# VCO.net
KiCad netlist of a schematic drawn in Altium Designer
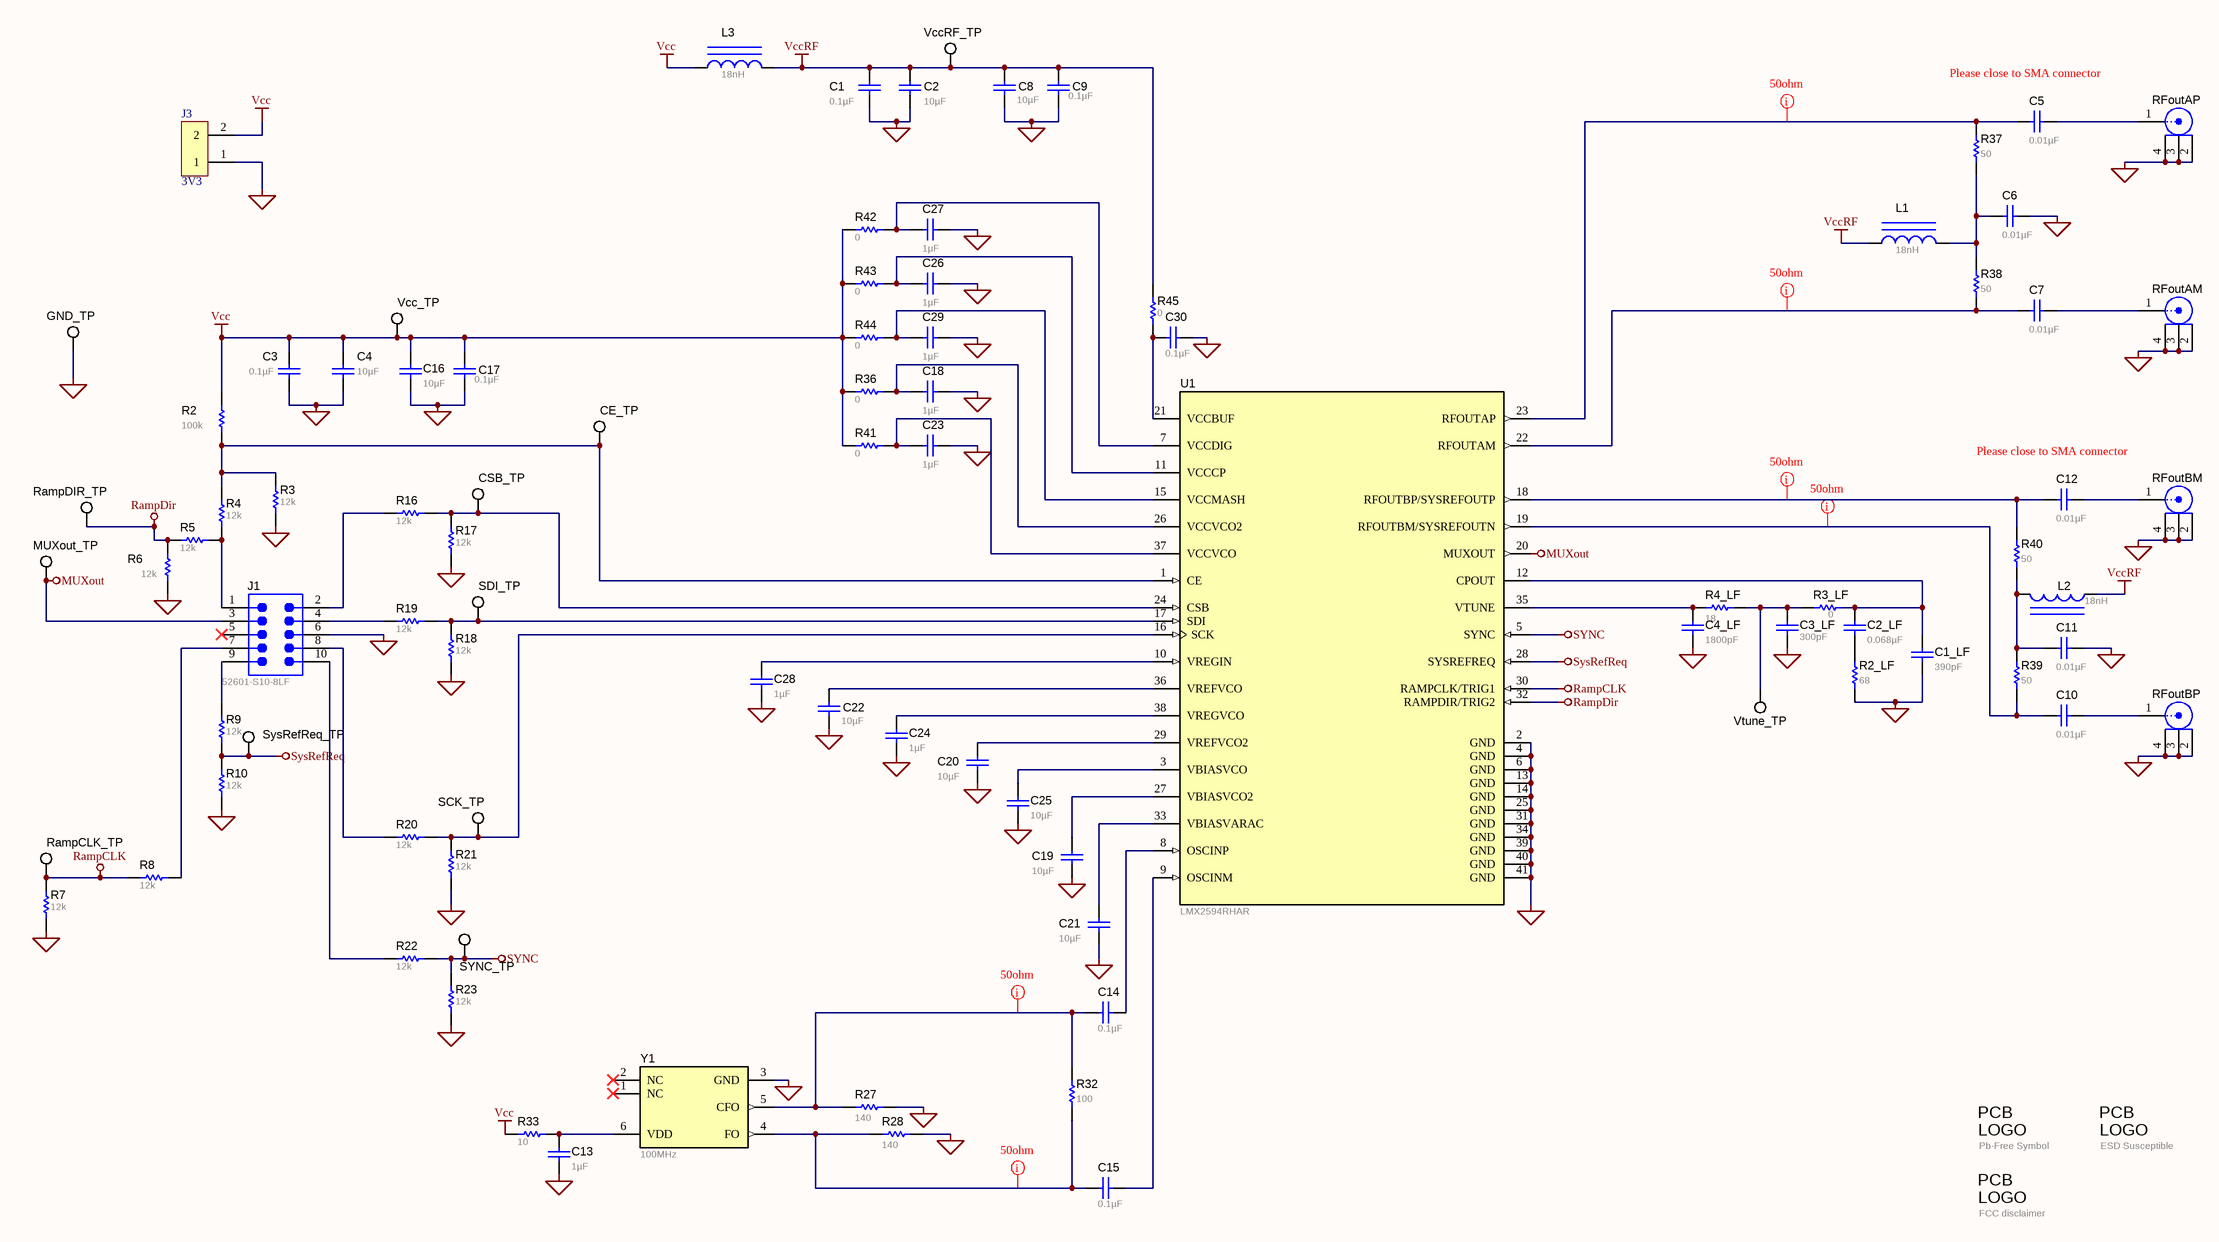
[diagram p0: VCO.SchDoc]

(export (version "E")
  (design (tool "Eeschema 10.0.6"))
  (components
    (comp (ref "C1")
      (value "0603YC104JAT2A")
      (footprint "0603")
      (description "CAP, CERM, 0.1uF, 16V, +/-5%, X7R, 0603")
      (fields
        (field (name "MANUFACTURER") "AVX")
        (field (name "VALUEDISPLAYED") "0.1µF")
        (field (name "DIGIKEYPARTNUMBER") "478-3726-1-ND")
        (field (name "PUBLISHER") "National Semiconductor")
      )
      (libsource (lib "Capacitor_Ceramic") (part "0603YC104JAT2A"))
    )
    (comp (ref "C1_LF")
      (value "C0603C391J5GACTU")
      (footprint "0603")
      (description "CAP, CERM, 390 pF, 50 V, +/- 5%, C0G/NP0, 0603")
      (fields
        (field (name "MANUFACTURER") "Kemet")
        (field (name "VALUEDISPLAYED") "390pF")
        (field (name "PUBLISHER") "Texas Instruments")
      )
      (libsource (lib "Capacitor_Ceramic") (part "C0603C391J5GACTU"))
    )
    (comp (ref "C2")
      (value "C0805C106K8PACTU")
      (footprint "0805")
      (description "CAP, CERM, 10uF, 10V, +/-10%, X5R, 0805")
      (fields
        (field (name "MANUFACTURER") "Kemet")
        (field (name "VALUEDISPLAYED") "10µF")
        (field (name "DIGIKEYPARTNUMBER") "399-4925-1-ND")
        (field (name "PUBLISHER") "National Semiconductor")
      )
      (libsource (lib "Capacitor_Ceramic") (part "C0805C106K8PACTU"))
    )
    (comp (ref "C2_LF")
      (value "GRM188R71H683KA93D")
      (footprint "0603")
      (description "CAP, CERM, 0.068 µF, 50 V, +/- 10%, X7R, 0603")
      (fields
        (field (name "MANUFACTURER") "MuRata")
        (field (name "VALUEDISPLAYED") "0.068µF")
        (field (name "PUBLISHER") "Texas Instruments")
      )
      (libsource (lib "Capacitor_Ceramic") (part "GRM188R71H683KA93D"))
    )
    (comp (ref "C3")
      (value "0603YC104JAT2A")
      (footprint "0603")
      (description "CAP, CERM, 0.1uF, 16V, +/-5%, X7R, 0603")
      (fields
        (field (name "MANUFACTURER") "AVX")
        (field (name "VALUEDISPLAYED") "0.1µF")
        (field (name "DIGIKEYPARTNUMBER") "478-3726-1-ND")
        (field (name "PUBLISHER") "National Semiconductor")
      )
      (libsource (lib "Capacitor_Ceramic") (part "0603YC104JAT2A"))
    )
    (comp (ref "C3_LF")
      (value "GRM1885C2A301JA01D")
      (footprint "0603")
      (description "CAP, CERM, 300pF, 100V, +/-5%, C0G/NP0, 0603")
      (fields
        (field (name "MANUFACTURER") "MuRata")
        (field (name "VALUEDISPLAYED") "300pF")
        (field (name "PUBLISHER") "Texas Instruments")
      )
      (libsource (lib "Capacitor_Ceramic") (part "GRM1885C2A301JA01D"))
    )
    (comp (ref "C4")
      (value "C0805C106K8PACTU")
      (footprint "0805")
      (description "CAP, CERM, 10uF, 10V, +/-10%, X5R, 0805")
      (fields
        (field (name "MANUFACTURER") "Kemet")
        (field (name "VALUEDISPLAYED") "10µF")
        (field (name "DIGIKEYPARTNUMBER") "399-4925-1-ND")
        (field (name "PUBLISHER") "National Semiconductor")
      )
      (libsource (lib "Capacitor_Ceramic") (part "C0805C106K8PACTU"))
    )
    (comp (ref "C4_LF")
      (value "GRM1885C1H182JA01D")
      (footprint "0603")
      (description "CAP, CERM, 1800 pF, 50 V, +/- 5%, C0G/NP0, 0603")
      (fields
        (field (name "MANUFACTURER") "MuRata")
        (field (name "VALUEDISPLAYED") "1800pF")
        (field (name "PUBLISHER") "Texas Instruments")
      )
      (libsource (lib "Capacitor_Ceramic") (part "GRM1885C1H182JA01D"))
    )
    (comp (ref "C5")
      (value "520L103KT16T")
      (footprint "0402_065")
      (description "CAP, CERM, 0.01 µF, 16 V, +/- 10%, X7R, 0402")
      (fields
        (field (name "VALUEDISPLAYED") "0.01µF")
        (field (name "MANUFACTURER") "AT Ceramics")
        (field (name "PUBLISHER") "Texas Instruments")
      )
      (libsource (lib "Capacitor_Ceramic") (part "520L103KT16T"))
    )
    (comp (ref "C6")
      (value "520L103KT16T")
      (footprint "0402_065")
      (description "CAP, CERM, 0.01 µF, 16 V, +/- 10%, X7R, 0402")
      (fields
        (field (name "VALUEDISPLAYED") "0.01µF")
        (field (name "MANUFACTURER") "AT Ceramics")
        (field (name "PUBLISHER") "Texas Instruments")
      )
      (libsource (lib "Capacitor_Ceramic") (part "520L103KT16T"))
    )
    (comp (ref "C7")
      (value "520L103KT16T")
      (footprint "0402_065")
      (description "CAP, CERM, 0.01 µF, 16 V, +/- 10%, X7R, 0402")
      (fields
        (field (name "VALUEDISPLAYED") "0.01µF")
        (field (name "MANUFACTURER") "AT Ceramics")
        (field (name "PUBLISHER") "Texas Instruments")
      )
      (libsource (lib "Capacitor_Ceramic") (part "520L103KT16T"))
    )
    (comp (ref "C8")
      (value "C0805C106K8PACTU")
      (footprint "0805")
      (description "CAP, CERM, 10uF, 10V, +/-10%, X5R, 0805")
      (fields
        (field (name "MANUFACTURER") "Kemet")
        (field (name "VALUEDISPLAYED") "10µF")
        (field (name "DIGIKEYPARTNUMBER") "399-4925-1-ND")
        (field (name "PUBLISHER") "National Semiconductor")
      )
      (libsource (lib "Capacitor_Ceramic") (part "C0805C106K8PACTU"))
    )
    (comp (ref "C9")
      (value "0603YC104JAT2A")
      (footprint "0603")
      (description "CAP, CERM, 0.1uF, 16V, +/-5%, X7R, 0603")
      (fields
        (field (name "MANUFACTURER") "AVX")
        (field (name "VALUEDISPLAYED") "0.1µF")
        (field (name "DIGIKEYPARTNUMBER") "478-3726-1-ND")
        (field (name "PUBLISHER") "National Semiconductor")
      )
      (libsource (lib "Capacitor_Ceramic") (part "0603YC104JAT2A"))
    )
    (comp (ref "C10")
      (value "520L103KT16T")
      (footprint "0402_065")
      (description "CAP, CERM, 0.01 µF, 16 V, +/- 10%, X7R, 0402")
      (fields
        (field (name "VALUEDISPLAYED") "0.01µF")
        (field (name "MANUFACTURER") "AT Ceramics")
        (field (name "PUBLISHER") "Texas Instruments")
      )
      (libsource (lib "Capacitor_Ceramic") (part "520L103KT16T"))
    )
    (comp (ref "C11")
      (value "520L103KT16T")
      (footprint "0402_065")
      (description "CAP, CERM, 0.01 µF, 16 V, +/- 10%, X7R, 0402")
      (fields
        (field (name "VALUEDISPLAYED") "0.01µF")
        (field (name "MANUFACTURER") "AT Ceramics")
        (field (name "PUBLISHER") "Texas Instruments")
      )
      (libsource (lib "Capacitor_Ceramic") (part "520L103KT16T"))
    )
    (comp (ref "C12")
      (value "520L103KT16T")
      (footprint "0402_065")
      (description "CAP, CERM, 0.01 µF, 16 V, +/- 10%, X7R, 0402")
      (fields
        (field (name "VALUEDISPLAYED") "0.01µF")
        (field (name "MANUFACTURER") "AT Ceramics")
        (field (name "PUBLISHER") "Texas Instruments")
      )
      (libsource (lib "Capacitor_Ceramic") (part "520L103KT16T"))
    )
    (comp (ref "C13")
      (value "C1608X7R1C105K080AC")
      (footprint "0603")
      (description "CAP, CERM, 1 µF, 16 V, +/- 10%, X7R, 0603")
      (fields
        (field (name "MANUFACTURER") "TDK")
        (field (name "VALUEDISPLAYED") "1µF")
        (field (name "PUBLISHER") "Texas Instruments")
      )
      (libsource (lib "Capacitor_Ceramic") (part "C1608X7R1C105K080AC"))
    )
    (comp (ref "C14")
      (value "0603YC104JAT2A")
      (footprint "0603L")
      (description "CAP, CERM, 0.1uF, 16V, +/-5%, X7R, 0603")
      (fields
        (field (name "MANUFACTURER") "AVX")
        (field (name "VALUEDISPLAYED") "0.1µF")
        (field (name "DIGIKEYPARTNUMBER") "478-3726-1-ND")
        (field (name "PUBLISHER") "National Semiconductor")
      )
      (libsource (lib "Capacitor_Ceramic") (part "0603YC104JAT2A"))
    )
    (comp (ref "C15")
      (value "0603YC104JAT2A")
      (footprint "0603L")
      (description "CAP, CERM, 0.1uF, 16V, +/-5%, X7R, 0603")
      (fields
        (field (name "MANUFACTURER") "AVX")
        (field (name "VALUEDISPLAYED") "0.1µF")
        (field (name "DIGIKEYPARTNUMBER") "478-3726-1-ND")
        (field (name "PUBLISHER") "National Semiconductor")
      )
      (libsource (lib "Capacitor_Ceramic") (part "0603YC104JAT2A"))
    )
    (comp (ref "C16")
      (value "C0805C106K8PACTU")
      (footprint "0805")
      (description "CAP, CERM, 10uF, 10V, +/-10%, X5R, 0805")
      (fields
        (field (name "MANUFACTURER") "Kemet")
        (field (name "VALUEDISPLAYED") "10µF")
        (field (name "DIGIKEYPARTNUMBER") "399-4925-1-ND")
        (field (name "PUBLISHER") "National Semiconductor")
      )
      (libsource (lib "Capacitor_Ceramic") (part "C0805C106K8PACTU"))
    )
    (comp (ref "C17")
      (value "0603YC104JAT2A")
      (footprint "0603")
      (description "CAP, CERM, 0.1uF, 16V, +/-5%, X7R, 0603")
      (fields
        (field (name "MANUFACTURER") "AVX")
        (field (name "VALUEDISPLAYED") "0.1µF")
        (field (name "DIGIKEYPARTNUMBER") "478-3726-1-ND")
        (field (name "PUBLISHER") "National Semiconductor")
      )
      (libsource (lib "Capacitor_Ceramic") (part "0603YC104JAT2A"))
    )
    (comp (ref "C18")
      (value "C1608X7R1C105K080AC")
      (footprint "0603")
      (description "CAP, CERM, 1 µF, 16 V, +/- 10%, X7R, 0603")
      (fields
        (field (name "MANUFACTURER") "TDK")
        (field (name "VALUEDISPLAYED") "1µF")
        (field (name "PUBLISHER") "Texas Instruments")
      )
      (libsource (lib "Capacitor_Ceramic") (part "C1608X7R1C105K080AC"))
    )
    (comp (ref "C19")
      (value "C1608X5R1A106M080AC")
      (footprint "0603")
      (description "CAP, CERM, 10 µF, 10 V, +/- 20%, X5R, 0603")
      (fields
        (field (name "MANUFACTURER") "TDK")
        (field (name "VALUEDISPLAYED") "10µF")
        (field (name "PUBLISHER") "Texas Instruments")
      )
      (libsource (lib "Capacitor_Ceramic") (part "C1608X5R1A106M080AC"))
    )
    (comp (ref "C20")
      (value "C1608X5R1A106M080AC")
      (footprint "0603")
      (description "CAP, CERM, 10 µF, 10 V, +/- 20%, X5R, 0603")
      (fields
        (field (name "MANUFACTURER") "TDK")
        (field (name "VALUEDISPLAYED") "10µF")
        (field (name "PUBLISHER") "Texas Instruments")
      )
      (libsource (lib "Capacitor_Ceramic") (part "C1608X5R1A106M080AC"))
    )
    (comp (ref "C21")
      (value "C1608X5R1A106M080AC")
      (footprint "0603")
      (description "CAP, CERM, 10 µF, 10 V, +/- 20%, X5R, 0603")
      (fields
        (field (name "MANUFACTURER") "TDK")
        (field (name "VALUEDISPLAYED") "10µF")
        (field (name "PUBLISHER") "Texas Instruments")
      )
      (libsource (lib "Capacitor_Ceramic") (part "C1608X5R1A106M080AC"))
    )
    (comp (ref "C22")
      (value "C1608X5R1A106M080AC")
      (footprint "0603")
      (description "CAP, CERM, 10 µF, 10 V, +/- 20%, X5R, 0603")
      (fields
        (field (name "MANUFACTURER") "TDK")
        (field (name "VALUEDISPLAYED") "10µF")
        (field (name "PUBLISHER") "Texas Instruments")
      )
      (libsource (lib "Capacitor_Ceramic") (part "C1608X5R1A106M080AC"))
    )
    (comp (ref "C23")
      (value "C1608X7R1C105K080AC")
      (footprint "0603")
      (description "CAP, CERM, 1 µF, 16 V, +/- 10%, X7R, 0603")
      (fields
        (field (name "MANUFACTURER") "TDK")
        (field (name "VALUEDISPLAYED") "1µF")
        (field (name "PUBLISHER") "Texas Instruments")
      )
      (libsource (lib "Capacitor_Ceramic") (part "C1608X7R1C105K080AC"))
    )
    (comp (ref "C24")
      (value "C1608X7R1C105K080AC")
      (footprint "0603")
      (description "CAP, CERM, 1 µF, 16 V, +/- 10%, X7R, 0603")
      (fields
        (field (name "MANUFACTURER") "TDK")
        (field (name "VALUEDISPLAYED") "1µF")
        (field (name "PUBLISHER") "Texas Instruments")
      )
      (libsource (lib "Capacitor_Ceramic") (part "C1608X7R1C105K080AC"))
    )
    (comp (ref "C25")
      (value "C1608X5R1A106M080AC")
      (footprint "0603")
      (description "CAP, CERM, 10 µF, 10 V, +/- 20%, X5R, 0603")
      (fields
        (field (name "MANUFACTURER") "TDK")
        (field (name "VALUEDISPLAYED") "10µF")
        (field (name "PUBLISHER") "Texas Instruments")
      )
      (libsource (lib "Capacitor_Ceramic") (part "C1608X5R1A106M080AC"))
    )
    (comp (ref "C26")
      (value "C1608X7R1C105K080AC")
      (footprint "0603L")
      (description "CAP, CERM, 1 µF, 16 V, +/- 10%, X7R, 0603")
      (fields
        (field (name "MANUFACTURER") "TDK")
        (field (name "VALUEDISPLAYED") "1µF")
        (field (name "PUBLISHER") "Texas Instruments")
      )
      (libsource (lib "Capacitor_Ceramic") (part "C1608X7R1C105K080AC"))
    )
    (comp (ref "C27")
      (value "C1608X7R1C105K080AC")
      (footprint "0603")
      (description "CAP, CERM, 1 µF, 16 V, +/- 10%, X7R, 0603")
      (fields
        (field (name "MANUFACTURER") "TDK")
        (field (name "VALUEDISPLAYED") "1µF")
        (field (name "PUBLISHER") "Texas Instruments")
      )
      (libsource (lib "Capacitor_Ceramic") (part "C1608X7R1C105K080AC"))
    )
    (comp (ref "C28")
      (value "C1608X7R1C105K080AC")
      (footprint "0603")
      (description "CAP, CERM, 1 µF, 16 V, +/- 10%, X7R, 0603")
      (fields
        (field (name "VALUEDISPLAYED") "1µF")
        (field (name "MANUFACTURER") "TDK")
        (field (name "PUBLISHER") "Texas Instruments")
      )
      (libsource (lib "Capacitor_Ceramic") (part "C1608X7R1C105K080AC"))
    )
    (comp (ref "C29")
      (value "C1608X7R1C105K080AC")
      (footprint "0603L")
      (description "CAP, CERM, 1 µF, 16 V, +/- 10%, X7R, 0603")
      (fields
        (field (name "MANUFACTURER") "TDK")
        (field (name "VALUEDISPLAYED") "1µF")
        (field (name "PUBLISHER") "Texas Instruments")
      )
      (libsource (lib "Capacitor_Ceramic") (part "C1608X7R1C105K080AC"))
    )
    (comp (ref "C30")
      (value "0603YC104JAT2A")
      (footprint "0603L")
      (description "CAP, CERM, 0.1uF, 16V, +/-5%, X7R, 0603")
      (fields
        (field (name "MANUFACTURER") "AVX")
        (field (name "VALUEDISPLAYED") "0.1µF")
        (field (name "DIGIKEYPARTNUMBER") "478-3726-1-ND")
        (field (name "PUBLISHER") "National Semiconductor")
      )
      (libsource (lib "Capacitor_Ceramic") (part "0603YC104JAT2A"))
    )
    (comp (ref "CE_TP")
      (value "5007")
      (footprint "Keystone5007")
      (description "Test Point, Compact, White, TH")
      (fields (field (name "MANUFACTURER") "Keystone") (field (name "PUBLISHER") "Texas Instruments"))
      (libsource (lib "Connectors_Keystone") (part "5007"))
    )
    (comp (ref "CSB_TP")
      (value "5007")
      (footprint "Keystone5007")
      (description "Test Point, Compact, White, TH")
      (fields (field (name "MANUFACTURER") "Keystone") (field (name "PUBLISHER") "Texas Instruments"))
      (libsource (lib "Connectors_Keystone") (part "5007"))
    )
    (comp (ref "GND_TP")
      (value "5007")
      (footprint "Keystone5007")
      (description "Test Point, Compact, White, TH")
      (fields (field (name "MANUFACTURER") "Keystone") (field (name "PUBLISHER") "Texas Instruments"))
      (libsource (lib "Connectors_Keystone") (part "5007"))
    )
    (comp (ref "J1")
      (value "52601-S10-8LF")
      (footprint "FCI_52601-S10-8LF")
      (description "Header (shrouded), 100mil, 5x2, Gold plated, SMD")
      (fields
        (field (name "MANUFACTURER") "FCI")
        (field (name "SYMBOLCREATOR") "a0412235")
        (field (name "PUBLISHER") "Texas Instruments")
      )
      (libsource (lib "Connectors_Other") (part "52601-S10-8LF"))
    )
    (comp (ref "J3")
      (value "3V3")
      (footprint "PHOENIX_1935161")
      (description "2 Position Wire to Board Terminal Block Horizontal with Board 0.197 _5.00mm_ Through Hole")
      (fields (field (name "MP") "1935161") (field (name "MF") "Phoenix Contact"))
      (libsource (lib "Schlib1") (part "1935161"))
    )
    (comp (ref "L1")
      (value "LQG15HS18NJ02D")
      (footprint "IND_LQG15H")
      (description "Inductor, Multilayer, Air Core, 18 nH, 0.3 A, 0.36 ohm, SMD")
      (fields
        (field (name "VALUEDISPLAYED") "18nH")
        (field (name "MANUFACTURER") "MuRata")
        (field (name "PUBLISHER") "Texas Instruments")
      )
      (libsource (lib "Inductor_MuRata") (part "LQG15HS18NJ02D"))
    )
    (comp (ref "L2")
      (value "LQG15HS18NJ02D")
      (footprint "IND_LQG15H")
      (description "Inductor, Multilayer, Air Core, 18 nH, 0.3 A, 0.36 ohm, SMD")
      (fields
        (field (name "VALUEDISPLAYED") "18nH")
        (field (name "MANUFACTURER") "MuRata")
        (field (name "PUBLISHER") "Texas Instruments")
      )
      (libsource (lib "Inductor_MuRata") (part "LQG15HS18NJ02D"))
    )
    (comp (ref "L3")
      (value "LQG15HS18NJ02D")
      (footprint "0402L")
      (description "Inductor, Multilayer, Air Core, 18 nH, 0.3 A, 0.36 ohm, SMD")
      (fields
        (field (name "VALUEDISPLAYED") "18nH")
        (field (name "MANUFACTURER") "MuRata")
        (field (name "PUBLISHER") "Texas Instruments")
      )
      (libsource (lib "Inductor_MuRata") (part "LQG15HS18NJ02D"))
    )
    (comp (ref "Logo1")
      (value "ESD Susceptible")
      (footprint "ESD_Overlay_Small")
      (description "ESD Susceptible Symbol")
      (fields (field (name "SYMBOLCREATOR") "codlsc") (field (name "PUBLISHER") "National Semiconductor"))
      (libsource (lib "Logos") (part "ESD_Susceptible"))
    )
    (comp (ref "Logo3")
      (value "Pb-Free Symbol")
      (footprint "Pb-Free_Overlay_Medium")
      (fields (field (name "SYMBOLCREATOR") "a0412235") (field (name "PUBLISHER") "Texas Instruments"))
      (libsource (lib "Logos") (part "Pb-Free"))
    )
    (comp (ref "Logo4")
      (value "FCC disclaimer")
      (footprint "FCC_disclaimer")
      (description "FCC_disclaimer")
      (fields (field (name "SYMBOLCREATOR") "codlsc") (field (name "PUBLISHER") "Texas Instruments"))
      (libsource (lib "Logos") (part "FCC_disclaimer"))
    )
    (comp (ref "MUXout_TP")
      (value "5007")
      (footprint "Keystone5007")
      (description "Test Point, Compact, White, TH")
      (fields (field (name "MANUFACTURER") "Keystone") (field (name "PUBLISHER") "Texas Instruments"))
      (libsource (lib "Connectors_Keystone") (part "5007"))
    )
    (comp (ref "R2")
      (value "CRCW0603100KJNEA")
      (footprint "0603")
      (description "RES, 100 k, 5%, 0.1 W, 0603")
      (fields
        (field (name "MANUFACTURER") "Vishay-Dale")
        (field (name "VALUEDISPLAYED") "100k")
        (field (name "PUBLISHER") "Texas Instruments")
      )
      (libsource (lib "Resistor_0603") (part "CRCW0603100KJNEA"))
    )
    (comp (ref "R2_LF")
      (value "CRCW060368R0JNEA")
      (footprint "0603")
      (description "RES, 68, 5%, 0.1 W, 0603")
      (fields
        (field (name "MANUFACTURER") "Vishay-Dale")
        (field (name "VALUEDISPLAYED") "68")
        (field (name "PUBLISHER") "Texas Instruments")
      )
      (libsource (lib "Resistor_0603") (part "CRCW060368R0JNEA"))
    )
    (comp (ref "R3")
      (value "12k")
      (footprint "0603")
      (description "RES, 12k ohm, 5%, 0.1W, 0603")
      (fields
        (field (name "MANUFACTURER") "Vishay-Dale")
        (field (name "PARTNUMBER") "CRCW060312K0JNEA")
        (field (name "PUBLISHER") "National Semiconductor")
      )
      (libsource (lib "Resistor_0603") (part "CRCW060312K0JNEA"))
    )
    (comp (ref "R3_LF")
      (value "CRCW06030000Z0EA")
      (footprint "0603")
      (description "RES, 0, 5%, 0.1 W, 0603")
      (fields
        (field (name "MANUFACTURER") "Vishay-Dale")
        (field (name "VALUEDISPLAYED") "0")
        (field (name "PUBLISHER") "Texas Instruments")
      )
      (libsource (lib "Resistor_0603") (part "CRCW06030000Z0EA"))
    )
    (comp (ref "R4")
      (value "12k")
      (footprint "0603")
      (description "RES, 12k ohm, 5%, 0.1W, 0603")
      (fields
        (field (name "MANUFACTURER") "Vishay-Dale")
        (field (name "PARTNUMBER") "CRCW060312K0JNEA")
        (field (name "PUBLISHER") "National Semiconductor")
      )
      (libsource (lib "Resistor_0603") (part "CRCW060312K0JNEA"))
    )
    (comp (ref "R4_LF")
      (value "CRCW060318R0JNEA")
      (footprint "0603")
      (description "RES, 18, 5%, 0.1 W, 0603")
      (fields
        (field (name "MANUFACTURER") "Vishay-Dale")
        (field (name "VALUEDISPLAYED") "18")
        (field (name "PUBLISHER") "Texas Instruments")
      )
      (libsource (lib "Resistor_0603") (part "CRCW060318R0JNEA"))
    )
    (comp (ref "R5")
      (value "12k")
      (footprint "0603")
      (description "RES, 12k ohm, 5%, 0.1W, 0603")
      (fields
        (field (name "MANUFACTURER") "Vishay-Dale")
        (field (name "PARTNUMBER") "CRCW060312K0JNEA")
        (field (name "PUBLISHER") "National Semiconductor")
      )
      (libsource (lib "Resistor_0603") (part "CRCW060312K0JNEA"))
    )
    (comp (ref "R6")
      (value "12k")
      (footprint "0603")
      (description "RES, 12k ohm, 5%, 0.1W, 0603")
      (fields
        (field (name "MANUFACTURER") "Vishay-Dale")
        (field (name "PARTNUMBER") "CRCW060312K0JNEA")
        (field (name "PUBLISHER") "National Semiconductor")
      )
      (libsource (lib "Resistor_0603") (part "CRCW060312K0JNEA"))
    )
    (comp (ref "R7")
      (value "12k")
      (footprint "0603")
      (description "RES, 12k ohm, 5%, 0.1W, 0603")
      (fields
        (field (name "MANUFACTURER") "Vishay-Dale")
        (field (name "PARTNUMBER") "CRCW060312K0JNEA")
        (field (name "PUBLISHER") "National Semiconductor")
      )
      (libsource (lib "Resistor_0603") (part "CRCW060312K0JNEA"))
    )
    (comp (ref "R8")
      (value "12k")
      (footprint "0603")
      (description "RES, 12k ohm, 5%, 0.1W, 0603")
      (fields
        (field (name "MANUFACTURER") "Vishay-Dale")
        (field (name "PARTNUMBER") "CRCW060312K0JNEA")
        (field (name "PUBLISHER") "National Semiconductor")
      )
      (libsource (lib "Resistor_0603") (part "CRCW060312K0JNEA"))
    )
    (comp (ref "R9")
      (value "12k")
      (footprint "0603")
      (description "RES, 12k ohm, 5%, 0.1W, 0603")
      (fields
        (field (name "MANUFACTURER") "Vishay-Dale")
        (field (name "PARTNUMBER") "CRCW060312K0JNEA")
        (field (name "PUBLISHER") "National Semiconductor")
      )
      (libsource (lib "Resistor_0603") (part "CRCW060312K0JNEA"))
    )
    (comp (ref "R10")
      (value "12k")
      (footprint "0603")
      (description "RES, 12k ohm, 5%, 0.1W, 0603")
      (fields
        (field (name "MANUFACTURER") "Vishay-Dale")
        (field (name "PARTNUMBER") "CRCW060312K0JNEA")
        (field (name "PUBLISHER") "National Semiconductor")
      )
      (libsource (lib "Resistor_0603") (part "CRCW060312K0JNEA"))
    )
    (comp (ref "R16")
      (value "12k")
      (footprint "0603")
      (description "RES, 12k ohm, 5%, 0.1W, 0603")
      (fields
        (field (name "MANUFACTURER") "Vishay-Dale")
        (field (name "PARTNUMBER") "CRCW060312K0JNEA")
        (field (name "PUBLISHER") "National Semiconductor")
      )
      (libsource (lib "Resistor_0603") (part "CRCW060312K0JNEA"))
    )
    (comp (ref "R17")
      (value "12k")
      (footprint "0603")
      (description "RES, 12k ohm, 5%, 0.1W, 0603")
      (fields
        (field (name "MANUFACTURER") "Vishay-Dale")
        (field (name "PARTNUMBER") "CRCW060312K0JNEA")
        (field (name "PUBLISHER") "National Semiconductor")
      )
      (libsource (lib "Resistor_0603") (part "CRCW060312K0JNEA"))
    )
    (comp (ref "R18")
      (value "12k")
      (footprint "0603")
      (description "RES, 12k ohm, 5%, 0.1W, 0603")
      (fields
        (field (name "MANUFACTURER") "Vishay-Dale")
        (field (name "PARTNUMBER") "CRCW060312K0JNEA")
        (field (name "PUBLISHER") "National Semiconductor")
      )
      (libsource (lib "Resistor_0603") (part "CRCW060312K0JNEA"))
    )
    (comp (ref "R19")
      (value "12k")
      (footprint "0603")
      (description "RES, 12k ohm, 5%, 0.1W, 0603")
      (fields
        (field (name "MANUFACTURER") "Vishay-Dale")
        (field (name "PARTNUMBER") "CRCW060312K0JNEA")
        (field (name "PUBLISHER") "National Semiconductor")
      )
      (libsource (lib "Resistor_0603") (part "CRCW060312K0JNEA"))
    )
    (comp (ref "R20")
      (value "12k")
      (footprint "0603")
      (description "RES, 12k ohm, 5%, 0.1W, 0603")
      (fields
        (field (name "MANUFACTURER") "Vishay-Dale")
        (field (name "PARTNUMBER") "CRCW060312K0JNEA")
        (field (name "PUBLISHER") "National Semiconductor")
      )
      (libsource (lib "Resistor_0603") (part "CRCW060312K0JNEA"))
    )
    (comp (ref "R21")
      (value "12k")
      (footprint "0603")
      (description "RES, 12k ohm, 5%, 0.1W, 0603")
      (fields
        (field (name "MANUFACTURER") "Vishay-Dale")
        (field (name "PARTNUMBER") "CRCW060312K0JNEA")
        (field (name "PUBLISHER") "National Semiconductor")
      )
      (libsource (lib "Resistor_0603") (part "CRCW060312K0JNEA"))
    )
    (comp (ref "R22")
      (value "12k")
      (footprint "0603")
      (description "RES, 12k ohm, 5%, 0.1W, 0603")
      (fields
        (field (name "MANUFACTURER") "Vishay-Dale")
        (field (name "PARTNUMBER") "CRCW060312K0JNEA")
        (field (name "PUBLISHER") "National Semiconductor")
      )
      (libsource (lib "Resistor_0603") (part "CRCW060312K0JNEA"))
    )
    (comp (ref "R23")
      (value "12k")
      (footprint "0603")
      (description "RES, 12k ohm, 5%, 0.1W, 0603")
      (fields
        (field (name "MANUFACTURER") "Vishay-Dale")
        (field (name "PARTNUMBER") "CRCW060312K0JNEA")
        (field (name "PUBLISHER") "National Semiconductor")
      )
      (libsource (lib "Resistor_0603") (part "CRCW060312K0JNEA"))
    )
    (comp (ref "R27")
      (value "CRCW0603140RFKEA")
      (footprint "0603")
      (description "RES, 140, 1%, 0.1 W, 0603")
      (fields
        (field (name "MANUFACTURER") "Vishay-Dale")
        (field (name "VALUEDISPLAYED") "140")
        (field (name "PUBLISHER") "Texas Instruments")
      )
      (libsource (lib "Resistor_0603") (part "CRCW0603140RFKEA"))
    )
    (comp (ref "R28")
      (value "CRCW0603140RFKEA")
      (footprint "0603")
      (description "RES, 140, 1%, 0.1 W, 0603")
      (fields
        (field (name "MANUFACTURER") "Vishay-Dale")
        (field (name "VALUEDISPLAYED") "140")
        (field (name "PUBLISHER") "Texas Instruments")
      )
      (libsource (lib "Resistor_0603") (part "CRCW0603140RFKEA"))
    )
    (comp (ref "R32")
      (value "CRCW0603100RFKEA")
      (footprint "0603L")
      (description "RES, 100, 1%, 0.1 W, 0603")
      (fields
        (field (name "MANUFACTURER") "Vishay-Dale")
        (field (name "VALUEDISPLAYED") "100")
        (field (name "PUBLISHER") "Texas Instruments")
      )
      (libsource (lib "Resistor_0603") (part "CRCW0603100RFKEA"))
    )
    (comp (ref "R33")
      (value "10")
      (footprint "0603")
      (description "RES, 10 ohm, 5%, 0.1W, 0603")
      (fields
        (field (name "PARTNUMBER") "CRCW060310R0JNEA")
        (field (name "MANUFACTURER") "Vishay-Dale")
        (field (name "PUBLISHER") "Texas Instruments")
      )
      (libsource (lib "Resistor_0603") (part "CRCW060310R0JNEA"))
    )
    (comp (ref "R36")
      (value "0")
      (footprint "0603")
      (description "RES, 0 ohm, 5%, 0.1W, 0603")
      (fields
        (field (name "MANUFACTURER") "Vishay-Dale")
        (field (name "PARTNUMBER") "CRCW06030000Z0EA")
        (field (name "PUBLISHER") "National Semiconductor")
      )
      (libsource (lib "Resistor_0603") (part "CRCW06030000Z0EA"))
    )
    (comp (ref "R37")
      (value "FC0402E50R0BST1")
      (footprint "0402L")
      (description "RES, 50, 0.1%, 0.05 W, 0402")
      (fields
        (field (name "VALUEDISPLAYED") "50")
        (field (name "MANUFACTURER") "Vishay-Dale")
        (field (name "PUBLISHER") "Texas Instruments")
      )
      (libsource (lib "Resistor_0402") (part "FC0402E50R0BST1"))
    )
    (comp (ref "R38")
      (value "FC0402E50R0BST1")
      (footprint "0402L")
      (description "RES, 50, 0.1%, 0.05 W, 0402")
      (fields
        (field (name "VALUEDISPLAYED") "50")
        (field (name "MANUFACTURER") "Vishay-Dale")
        (field (name "PUBLISHER") "Texas Instruments")
      )
      (libsource (lib "Resistor_0402") (part "FC0402E50R0BST1"))
    )
    (comp (ref "R39")
      (value "FC0402E50R0BST1")
      (footprint "0402L")
      (description "RES, 50, 0.1%, 0.05 W, 0402")
      (fields
        (field (name "VALUEDISPLAYED") "50")
        (field (name "MANUFACTURER") "Vishay-Dale")
        (field (name "PUBLISHER") "Texas Instruments")
      )
      (libsource (lib "Resistor_0402") (part "FC0402E50R0BST1"))
    )
    (comp (ref "R40")
      (value "FC0402E50R0BST1")
      (footprint "0402L")
      (description "RES, 50, 0.1%, 0.05 W, 0402")
      (fields
        (field (name "VALUEDISPLAYED") "50")
        (field (name "MANUFACTURER") "Vishay-Dale")
        (field (name "PUBLISHER") "Texas Instruments")
      )
      (libsource (lib "Resistor_0402") (part "FC0402E50R0BST1"))
    )
    (comp (ref "R41")
      (value "0")
      (footprint "0603")
      (description "RES, 0 ohm, 5%, 0.1W, 0603")
      (fields
        (field (name "MANUFACTURER") "Vishay-Dale")
        (field (name "PARTNUMBER") "CRCW06030000Z0EA")
        (field (name "PUBLISHER") "National Semiconductor")
      )
      (libsource (lib "Resistor_0603") (part "CRCW06030000Z0EA"))
    )
    (comp (ref "R42")
      (value "0")
      (footprint "0603")
      (description "RES, 0 ohm, 5%, 0.1W, 0603")
      (fields
        (field (name "MANUFACTURER") "Vishay-Dale")
        (field (name "PARTNUMBER") "CRCW06030000Z0EA")
        (field (name "PUBLISHER") "National Semiconductor")
      )
      (libsource (lib "Resistor_0603") (part "CRCW06030000Z0EA"))
    )
    (comp (ref "R43")
      (value "0")
      (footprint "0603L")
      (description "RES, 0 ohm, 5%, 0.1W, 0603")
      (fields
        (field (name "MANUFACTURER") "Vishay-Dale")
        (field (name "PARTNUMBER") "CRCW06030000Z0EA")
        (field (name "PUBLISHER") "National Semiconductor")
      )
      (libsource (lib "Resistor_0603") (part "CRCW06030000Z0EA"))
    )
    (comp (ref "R44")
      (value "0")
      (footprint "0603L")
      (description "RES, 0 ohm, 5%, 0.1W, 0603")
      (fields
        (field (name "MANUFACTURER") "Vishay-Dale")
        (field (name "PARTNUMBER") "CRCW06030000Z0EA")
        (field (name "PUBLISHER") "National Semiconductor")
      )
      (libsource (lib "Resistor_0603") (part "CRCW06030000Z0EA"))
    )
    (comp (ref "R45")
      (value "0")
      (footprint "0603L")
      (description "RES, 0 ohm, 5%, 0.1W, 0603")
      (fields
        (field (name "MANUFACTURER") "Vishay-Dale")
        (field (name "PARTNUMBER") "CRCW06030000Z0EA")
        (field (name "PUBLISHER") "National Semiconductor")
      )
      (libsource (lib "Resistor_0603") (part "CRCW06030000Z0EA"))
    )
    (comp (ref "RampCLK_TP")
      (value "5007")
      (footprint "Keystone5007")
      (description "Test Point, Compact, White, TH")
      (fields (field (name "MANUFACTURER") "Keystone") (field (name "PUBLISHER") "Texas Instruments"))
      (libsource (lib "Connectors_Keystone") (part "5007"))
    )
    (comp (ref "RampDIR_TP")
      (value "5007")
      (footprint "Keystone5007")
      (description "Test Point, Compact, White, TH")
      (fields (field (name "MANUFACTURER") "Keystone") (field (name "PUBLISHER") "Texas Instruments"))
      (libsource (lib "Connectors_Keystone") (part "5007"))
    )
    (comp (ref "RFoutAM")
      (value "142-0771-831")
      (footprint "Johnson_142-0771-831")
      (description "JACK, SMA, 50 Ohm, Gold, Edge Mount")
      (fields
        (field (name "MANUFACTURER") "Johnson")
        (field (name "SYMBOLCREATOR") "Altium")
        (field (name "PUBLISHER") "Texas Instruments")
      )
      (libsource (lib "Connectors_Other") (part "142-0771-831"))
    )
    (comp (ref "RFoutAP")
      (value "142-0771-831")
      (footprint "Johnson_142-0771-831")
      (description "JACK, SMA, 50 Ohm, Gold, Edge Mount")
      (fields
        (field (name "MANUFACTURER") "Johnson")
        (field (name "SYMBOLCREATOR") "Altium")
        (field (name "PUBLISHER") "Texas Instruments")
      )
      (libsource (lib "Connectors_Other") (part "142-0771-831"))
    )
    (comp (ref "RFoutBM")
      (value "142-0771-831")
      (footprint "Johnson_142-0771-831")
      (description "JACK, SMA, 50 Ohm, Gold, Edge Mount")
      (fields
        (field (name "MANUFACTURER") "Johnson")
        (field (name "SYMBOLCREATOR") "Altium")
        (field (name "PUBLISHER") "Texas Instruments")
      )
      (libsource (lib "Connectors_Other") (part "142-0771-831"))
    )
    (comp (ref "RFoutBP")
      (value "142-0771-831")
      (footprint "Johnson_142-0771-831")
      (description "JACK, SMA, 50 Ohm, Gold, Edge Mount")
      (fields
        (field (name "MANUFACTURER") "Johnson")
        (field (name "SYMBOLCREATOR") "Altium")
        (field (name "PUBLISHER") "Texas Instruments")
      )
      (libsource (lib "Connectors_Other") (part "142-0771-831"))
    )
    (comp (ref "SCK_TP")
      (value "5007")
      (footprint "Keystone5007")
      (description "Test Point, Compact, White, TH")
      (fields (field (name "MANUFACTURER") "Keystone") (field (name "PUBLISHER") "Texas Instruments"))
      (libsource (lib "Connectors_Keystone") (part "5007"))
    )
    (comp (ref "SDI_TP")
      (value "5007")
      (footprint "Keystone5007")
      (description "Test Point, Compact, White, TH")
      (fields (field (name "MANUFACTURER") "Keystone") (field (name "PUBLISHER") "Texas Instruments"))
      (libsource (lib "Connectors_Keystone") (part "5007"))
    )
    (comp (ref "SYNC_TP")
      (value "5007")
      (footprint "Keystone5007")
      (description "Test Point, Compact, White, TH")
      (fields (field (name "MANUFACTURER") "Keystone") (field (name "PUBLISHER") "Texas Instruments"))
      (libsource (lib "Connectors_Keystone") (part "5007"))
    )
    (comp (ref "SysRefReq_TP")
      (value "5007")
      (footprint "Keystone5007")
      (description "Test Point, Compact, White, TH")
      (fields (field (name "MANUFACTURER") "Keystone") (field (name "PUBLISHER") "Texas Instruments"))
      (libsource (lib "Connectors_Keystone") (part "5007"))
    )
    (comp (ref "U1")
      (value "LMX2594RHAR")
      (footprint "RHA0040A")
      (description "High Performance, Wideband PLLatinum RF Synthesizer, RHA0040A (VQFN-40)")
      (fields
        (field (name "ALTERNATE PARTNUMBER") "LMX2594RHAT")
        (field (name "MANUFACTURER") "Texas Instruments")
        (field (name "SYMBOLCREATOR") "Altium")
        (field (name "PUBLISHER") "Texas Instruments")
      )
      (libsource (lib "TI_Pre_RTM") (part "LMX2594RHAR"))
    )
    (comp (ref "VccRF_TP")
      (value "5007")
      (footprint "Keystone5007")
      (description "Test Point, Compact, White, TH")
      (fields (field (name "MANUFACTURER") "Keystone") (field (name "PUBLISHER") "Texas Instruments"))
      (libsource (lib "Connectors_Keystone") (part "5007"))
    )
    (comp (ref "Vcc_TP")
      (value "5007")
      (footprint "Keystone5007")
      (description "Test Point, Compact, White, TH")
      (fields (field (name "MANUFACTURER") "Keystone") (field (name "PUBLISHER") "Texas Instruments"))
      (libsource (lib "Connectors_Keystone") (part "5007"))
    )
    (comp (ref "Vtune_TP")
      (value "5007")
      (footprint "Keystone5007")
      (description "Test Point, Compact, White, TH")
      (fields (field (name "MANUFACTURER") "Keystone") (field (name "PUBLISHER") "Texas Instruments"))
      (libsource (lib "Connectors_Keystone") (part "5007"))
    )
    (comp (ref "Y1")
      (value "VC-708-EDE-FNXN-100M000000")
      (footprint "Vectron_VC-708")
      (description "Crystal Oscillator, 100MHz, LVDS, 3.3V, SMD")
      (fields
        (field (name "FREQUENCY") "100MHz")
        (field (name "MANUFACTURER") "Vectron")
        (field (name "SYMBOLCREATOR") "Altium")
        (field (name "PUBLISHER") "Texas Instruments")
      )
      (libsource (lib "Oscillators") (part "VC-708-EDE-FNXN-100M000000"))
    )
  )
  (nets
    (net (code "1") (name "GND") (class "Default")
      (node (ref "C1") (pin "1") (pinfunction "1_1") (pintype "passive"))
      (node (ref "C11") (pin "1") (pinfunction "1_1") (pintype "passive"))
      (node (ref "C13") (pin "2") (pinfunction "2_2") (pintype "passive"))
      (node (ref "C16") (pin "1") (pinfunction "1_1") (pintype "passive"))
      (node (ref "C17") (pin "1") (pinfunction "1_1") (pintype "passive"))
      (node (ref "C18") (pin "1") (pinfunction "1_1") (pintype "passive"))
      (node (ref "C19") (pin "1") (pinfunction "1_1") (pintype "passive"))
      (node (ref "C1_LF") (pin "2") (pinfunction "2_2") (pintype "passive"))
      (node (ref "C2") (pin "1") (pinfunction "1_1") (pintype "passive"))
      (node (ref "C20") (pin "2") (pinfunction "2_2") (pintype "passive"))
      (node (ref "C21") (pin "1") (pinfunction "1_1") (pintype "passive"))
      (node (ref "C22") (pin "2") (pinfunction "2_2") (pintype "passive"))
      (node (ref "C23") (pin "1") (pinfunction "1_1") (pintype "passive"))
      (node (ref "C24") (pin "1") (pinfunction "1_1") (pintype "passive"))
      (node (ref "C25") (pin "2") (pinfunction "2_2") (pintype "passive"))
      (node (ref "C26") (pin "1") (pinfunction "1_1") (pintype "passive"))
      (node (ref "C27") (pin "1") (pinfunction "1_1") (pintype "passive"))
      (node (ref "C28") (pin "1") (pinfunction "1_1") (pintype "passive"))
      (node (ref "C29") (pin "2") (pinfunction "2_2") (pintype "passive"))
      (node (ref "C3") (pin "1") (pinfunction "1_1") (pintype "passive"))
      (node (ref "C30") (pin "1") (pinfunction "1_1") (pintype "passive"))
      (node (ref "C3_LF") (pin "2") (pinfunction "2_2") (pintype "passive"))
      (node (ref "C4") (pin "1") (pinfunction "1_1") (pintype "passive"))
      (node (ref "C4_LF") (pin "1") (pinfunction "1_1") (pintype "passive"))
      (node (ref "C6") (pin "1") (pinfunction "1_1") (pintype "passive"))
      (node (ref "C8") (pin "1") (pinfunction "1_1") (pintype "passive"))
      (node (ref "C9") (pin "1") (pinfunction "1_1") (pintype "passive"))
      (node (ref "GND_TP") (pin "1") (pintype "passive"))
      (node (ref "J1") (pin "6") (pinfunction "6_6") (pintype "passive"))
      (node (ref "J3") (pin "1") (pinfunction "1_1") (pintype "passive"))
      (node (ref "R10") (pin "1") (pinfunction "1_1") (pintype "passive"))
      (node (ref "R17") (pin "1") (pinfunction "1_1") (pintype "passive"))
      (node (ref "R18") (pin "1") (pinfunction "1_1") (pintype "passive"))
      (node (ref "R21") (pin "1") (pinfunction "1_1") (pintype "passive"))
      (node (ref "R23") (pin "1") (pinfunction "1_1") (pintype "passive"))
      (node (ref "R27") (pin "1") (pinfunction "1_1") (pintype "passive"))
      (node (ref "R28") (pin "1") (pinfunction "1_1") (pintype "passive"))
      (node (ref "R2_LF") (pin "2") (pinfunction "2_2") (pintype "passive"))
      (node (ref "R3") (pin "1") (pinfunction "1_1") (pintype "passive"))
      (node (ref "R6") (pin "1") (pinfunction "1_1") (pintype "passive"))
      (node (ref "R7") (pin "1") (pinfunction "1_1") (pintype "passive"))
      (node (ref "RFoutAM") (pin "2") (pinfunction "2_2") (pintype "passive"))
      (node (ref "RFoutAM") (pin "3") (pinfunction "3_3") (pintype "passive"))
      (node (ref "RFoutAM") (pin "4") (pinfunction "4_4") (pintype "passive"))
      (node (ref "RFoutAP") (pin "2") (pinfunction "2_2") (pintype "passive"))
      (node (ref "RFoutAP") (pin "3") (pinfunction "3_3") (pintype "passive"))
      (node (ref "RFoutAP") (pin "4") (pinfunction "4_4") (pintype "passive"))
      (node (ref "RFoutBM") (pin "2") (pinfunction "2_2") (pintype "passive"))
      (node (ref "RFoutBM") (pin "3") (pinfunction "3_3") (pintype "passive"))
      (node (ref "RFoutBM") (pin "4") (pinfunction "4_4") (pintype "passive"))
      (node (ref "RFoutBP") (pin "2") (pinfunction "2_2") (pintype "passive"))
      (node (ref "RFoutBP") (pin "3") (pinfunction "3_3") (pintype "passive"))
      (node (ref "RFoutBP") (pin "4") (pinfunction "4_4") (pintype "passive"))
      (node (ref "U1") (pin "13") (pinfunction "GND_13") (pintype "power_in"))
      (node (ref "U1") (pin "14") (pinfunction "GND_14") (pintype "power_in"))
      (node (ref "U1") (pin "2") (pinfunction "GND_2") (pintype "power_in"))
      (node (ref "U1") (pin "25") (pinfunction "GND_25") (pintype "power_in"))
      (node (ref "U1") (pin "31") (pinfunction "GND_31") (pintype "power_in"))
      (node (ref "U1") (pin "34") (pinfunction "GND_34") (pintype "power_in"))
      (node (ref "U1") (pin "39") (pinfunction "GND_39") (pintype "power_in"))
      (node (ref "U1") (pin "4") (pinfunction "GND_4") (pintype "power_in"))
      (node (ref "U1") (pin "40") (pinfunction "GND_40") (pintype "power_in"))
      (node (ref "U1") (pin "41") (pinfunction "GND_41") (pintype "power_in"))
      (node (ref "U1") (pin "6") (pinfunction "GND_6") (pintype "power_in"))
      (node (ref "Y1") (pin "3") (pinfunction "GND_3") (pintype "power_in"))
    )
    (net (code "2") (name "MUXout") (class "Default")
      (node (ref "J1") (pin "3") (pinfunction "3_3") (pintype "passive"))
      (node (ref "MUXout_TP") (pin "1") (pintype "passive"))
      (node (ref "U1") (pin "20") (pinfunction "MUXOUT_20") (pintype "output"))
    )
    (net (code "3") (name "Net-(C2_LF-Pad2)") (class "Default")
      (node (ref "C2_LF") (pin "2") (pinfunction "2_2") (pintype "passive"))
      (node (ref "R2_LF") (pin "1") (pinfunction "1_1") (pintype "passive"))
    )
    (net (code "4") (name "Net-(C3_LF-Pad1)") (class "Default")
      (node (ref "C3_LF") (pin "1") (pinfunction "1_1") (pintype "passive"))
      (node (ref "R3_LF") (pin "2") (pinfunction "2_2") (pintype "passive"))
      (node (ref "R4_LF") (pin "2") (pinfunction "2_2") (pintype "passive"))
      (node (ref "Vtune_TP") (pin "1") (pintype "passive"))
    )
    (net (code "5") (name "Net-(C5-Pad1)") (class "Default")
      (node (ref "C5") (pin "1") (pinfunction "1_1") (pintype "passive"))
      (node (ref "RFoutAP") (pin "1") (pinfunction "1_1") (pintype "passive"))
    )
    (net (code "6") (name "Net-(C6-Pad2)") (class "Default")
      (node (ref "C6") (pin "2") (pinfunction "2_2") (pintype "passive"))
      (node (ref "L1") (pin "2") (pinfunction "2_2") (pintype "passive"))
      (node (ref "R37") (pin "2") (pinfunction "2_2") (pintype "passive"))
      (node (ref "R38") (pin "2") (pinfunction "2_2") (pintype "passive"))
    )
    (net (code "7") (name "Net-(C7-Pad1)") (class "Default")
      (node (ref "C7") (pin "1") (pinfunction "1_1") (pintype "passive"))
      (node (ref "RFoutAM") (pin "1") (pinfunction "1_1") (pintype "passive"))
    )
    (net (code "8") (name "Net-(C10-Pad1)") (class "Default")
      (node (ref "C10") (pin "1") (pinfunction "1_1") (pintype "passive"))
      (node (ref "RFoutBP") (pin "1") (pinfunction "1_1") (pintype "passive"))
    )
    (net (code "9") (name "Net-(C11-Pad2)") (class "Default")
      (node (ref "C11") (pin "2") (pinfunction "2_2") (pintype "passive"))
      (node (ref "L2") (pin "2") (pinfunction "2_2") (pintype "passive"))
      (node (ref "R39") (pin "2") (pinfunction "2_2") (pintype "passive"))
      (node (ref "R40") (pin "1") (pinfunction "1_1") (pintype "passive"))
    )
    (net (code "10") (name "Net-(C12-Pad1)") (class "Default")
      (node (ref "C12") (pin "1") (pinfunction "1_1") (pintype "passive"))
      (node (ref "RFoutBM") (pin "1") (pinfunction "1_1") (pintype "passive"))
    )
    (net (code "11") (name "Net-(J1-Pad1)") (class "Default")
      (node (ref "J1") (pin "1") (pinfunction "1_1") (pintype "passive"))
      (node (ref "R4") (pin "1") (pinfunction "1_1") (pintype "passive"))
      (node (ref "R5") (pin "2") (pinfunction "2_2") (pintype "passive"))
    )
    (net (code "12") (name "Net-(J1-Pad2)") (class "Default")
      (node (ref "J1") (pin "2") (pinfunction "2_2") (pintype "passive"))
      (node (ref "R16") (pin "1") (pinfunction "1_1") (pintype "passive"))
    )
    (net (code "13") (name "Net-(J1-Pad4)") (class "Default")
      (node (ref "J1") (pin "4") (pinfunction "4_4") (pintype "passive"))
      (node (ref "R19") (pin "2") (pinfunction "2_2") (pintype "passive"))
    )
    (net (code "14") (name "Net-(J1-Pad7)") (class "Default")
      (node (ref "J1") (pin "7") (pinfunction "7_7") (pintype "passive"))
      (node (ref "R8") (pin "1") (pinfunction "1_1") (pintype "passive"))
    )
    (net (code "15") (name "Net-(J1-Pad8)") (class "Default")
      (node (ref "J1") (pin "8") (pinfunction "8_8") (pintype "passive"))
      (node (ref "R20") (pin "1") (pinfunction "1_1") (pintype "passive"))
    )
    (net (code "16") (name "Net-(J1-Pad9)") (class "Default")
      (node (ref "J1") (pin "9") (pinfunction "9_9") (pintype "passive"))
      (node (ref "R9") (pin "1") (pinfunction "1_1") (pintype "passive"))
    )
    (net (code "17") (name "Net-(J1-Pad10)") (class "Default")
      (node (ref "J1") (pin "10") (pinfunction "10_10") (pintype "passive"))
      (node (ref "R22") (pin "1") (pinfunction "1_1") (pintype "passive"))
    )
    (net (code "18") (name "Net-(U1-CE)") (class "Default")
      (node (ref "CE_TP") (pin "1") (pintype "passive"))
      (node (ref "R2") (pin "2") (pinfunction "2_2") (pintype "passive"))
      (node (ref "R3") (pin "2") (pinfunction "2_2") (pintype "passive"))
      (node (ref "R4") (pin "2") (pinfunction "2_2") (pintype "passive"))
      (node (ref "U1") (pin "1") (pinfunction "CE_1") (pintype "input"))
    )
    (net (code "19") (name "Net-(U1-CPOUT)") (class "Default")
      (node (ref "C1_LF") (pin "1") (pinfunction "1_1") (pintype "passive"))
      (node (ref "C2_LF") (pin "1") (pinfunction "1_1") (pintype "passive"))
      (node (ref "R3_LF") (pin "1") (pinfunction "1_1") (pintype "passive"))
      (node (ref "U1") (pin "12") (pinfunction "CPOUT_12") (pintype "passive"))
    )
    (net (code "20") (name "Net-(U1-CSB)") (class "Default")
      (node (ref "CSB_TP") (pin "1") (pintype "passive"))
      (node (ref "R16") (pin "2") (pinfunction "2_2") (pintype "passive"))
      (node (ref "R17") (pin "2") (pinfunction "2_2") (pintype "passive"))
      (node (ref "U1") (pin "24") (pinfunction "CSB_24") (pintype "input"))
    )
    (net (code "21") (name "Net-(U1-OSCINM)") (class "Default")
      (node (ref "C15") (pin "2") (pinfunction "2_2") (pintype "passive"))
      (node (ref "U1") (pin "9") (pinfunction "OSCINM_9") (pintype "input"))
    )
    (net (code "22") (name "Net-(U1-OSCINP)") (class "Default")
      (node (ref "C14") (pin "2") (pinfunction "2_2") (pintype "passive"))
      (node (ref "U1") (pin "8") (pinfunction "OSCINP_8") (pintype "input"))
    )
    (net (code "23") (name "Net-(U1-RFOUTAM)") (class "Default")
      (node (ref "C7") (pin "2") (pinfunction "2_2") (pintype "passive"))
      (node (ref "R38") (pin "1") (pinfunction "1_1") (pintype "passive"))
      (node (ref "U1") (pin "22") (pinfunction "RFOUTAM_22") (pintype "output"))
    )
    (net (code "24") (name "Net-(U1-RFOUTAP)") (class "Default")
      (node (ref "C5") (pin "2") (pinfunction "2_2") (pintype "passive"))
      (node (ref "R37") (pin "1") (pinfunction "1_1") (pintype "passive"))
      (node (ref "U1") (pin "23") (pinfunction "RFOUTAP_23") (pintype "output"))
    )
    (net (code "25") (name "Net-(U1-RFOUTBM{slash}SYSREFOUTN)") (class "Default")
      (node (ref "C10") (pin "2") (pinfunction "2_2") (pintype "passive"))
      (node (ref "R39") (pin "1") (pinfunction "1_1") (pintype "passive"))
      (node (ref "U1") (pin "19") (pinfunction "RFOUTBM/SYSREFOUTN_19") (pintype "output"))
    )
    (net (code "26") (name "Net-(U1-RFOUTBP{slash}SYSREFOUTP)") (class "Default")
      (node (ref "C12") (pin "2") (pinfunction "2_2") (pintype "passive"))
      (node (ref "R40") (pin "2") (pinfunction "2_2") (pintype "passive"))
      (node (ref "U1") (pin "18") (pinfunction "RFOUTBP/SYSREFOUTP_18") (pintype "output"))
    )
    (net (code "27") (name "Net-(U1-SCK)") (class "Default")
      (node (ref "R20") (pin "2") (pinfunction "2_2") (pintype "passive"))
      (node (ref "R21") (pin "2") (pinfunction "2_2") (pintype "passive"))
      (node (ref "SCK_TP") (pin "1") (pintype "passive"))
      (node (ref "U1") (pin "16") (pinfunction "SCK_16") (pintype "input"))
    )
    (net (code "28") (name "Net-(U1-SDI)") (class "Default")
      (node (ref "R18") (pin "2") (pinfunction "2_2") (pintype "passive"))
      (node (ref "R19") (pin "1") (pinfunction "1_1") (pintype "passive"))
      (node (ref "SDI_TP") (pin "1") (pintype "passive"))
      (node (ref "U1") (pin "17") (pinfunction "SDI_17") (pintype "input"))
    )
    (net (code "29") (name "Net-(U1-VBIASVARAC)") (class "Default")
      (node (ref "C21") (pin "2") (pinfunction "2_2") (pintype "passive"))
      (node (ref "U1") (pin "33") (pinfunction "VBIASVARAC_33") (pintype "passive"))
    )
    (net (code "30") (name "Net-(U1-VBIASVCO)") (class "Default")
      (node (ref "C25") (pin "1") (pinfunction "1_1") (pintype "passive"))
      (node (ref "U1") (pin "3") (pinfunction "VBIASVCO_3") (pintype "passive"))
    )
    (net (code "31") (name "Net-(U1-VBIASVCO2)") (class "Default")
      (node (ref "C19") (pin "2") (pinfunction "2_2") (pintype "passive"))
      (node (ref "U1") (pin "27") (pinfunction "VBIASVCO2_27") (pintype "passive"))
    )
    (net (code "32") (name "Net-(U1-VCCBUF)") (class "Default")
      (node (ref "C30") (pin "2") (pinfunction "2_2") (pintype "passive"))
      (node (ref "R45") (pin "2") (pinfunction "2_2") (pintype "passive"))
      (node (ref "U1") (pin "21") (pinfunction "VCCBUF_21") (pintype "power_in"))
    )
    (net (code "33") (name "Net-(U1-VCCCP)") (class "Default")
      (node (ref "C26") (pin "2") (pinfunction "2_2") (pintype "passive"))
      (node (ref "R43") (pin "2") (pinfunction "2_2") (pintype "passive"))
      (node (ref "U1") (pin "11") (pinfunction "VCCCP_11") (pintype "power_in"))
    )
    (net (code "34") (name "Net-(U1-VCCDIG)") (class "Default")
      (node (ref "C27") (pin "2") (pinfunction "2_2") (pintype "passive"))
      (node (ref "R42") (pin "2") (pinfunction "2_2") (pintype "passive"))
      (node (ref "U1") (pin "7") (pinfunction "VCCDIG_7") (pintype "power_in"))
    )
    (net (code "35") (name "Net-(U1-VCCMASH)") (class "Default")
      (node (ref "C29") (pin "1") (pinfunction "1_1") (pintype "passive"))
      (node (ref "R44") (pin "2") (pinfunction "2_2") (pintype "passive"))
      (node (ref "U1") (pin "15") (pinfunction "VCCMASH_15") (pintype "power_in"))
    )
    (net (code "36") (name "Net-(U1-VCCVCO)") (class "Default")
      (node (ref "C23") (pin "2") (pinfunction "2_2") (pintype "passive"))
      (node (ref "R41") (pin "1") (pinfunction "1_1") (pintype "passive"))
      (node (ref "U1") (pin "37") (pinfunction "VCCVCO_37") (pintype "power_in"))
    )
    (net (code "37") (name "Net-(U1-VCCVCO2)") (class "Default")
      (node (ref "C18") (pin "2") (pinfunction "2_2") (pintype "passive"))
      (node (ref "R36") (pin "1") (pinfunction "1_1") (pintype "passive"))
      (node (ref "U1") (pin "26") (pinfunction "VCCVCO2_26") (pintype "power_in"))
    )
    (net (code "38") (name "Net-(U1-VREFVCO)") (class "Default")
      (node (ref "C22") (pin "1") (pinfunction "1_1") (pintype "passive"))
      (node (ref "U1") (pin "36") (pinfunction "VREFVCO_36") (pintype "passive"))
    )
    (net (code "39") (name "Net-(U1-VREFVCO2)") (class "Default")
      (node (ref "C20") (pin "1") (pinfunction "1_1") (pintype "passive"))
      (node (ref "U1") (pin "29") (pinfunction "VREFVCO2_29") (pintype "passive"))
    )
    (net (code "40") (name "Net-(U1-VREGIN)") (class "Default")
      (node (ref "C28") (pin "2") (pinfunction "2_2") (pintype "passive"))
      (node (ref "U1") (pin "10") (pinfunction "VREGIN_10") (pintype "input"))
    )
    (net (code "41") (name "Net-(U1-VREGVCO)") (class "Default")
      (node (ref "C24") (pin "2") (pinfunction "2_2") (pintype "passive"))
      (node (ref "U1") (pin "38") (pinfunction "VREGVCO_38") (pintype "passive"))
    )
    (net (code "42") (name "Net-(U1-VTUNE)") (class "Default")
      (node (ref "C4_LF") (pin "2") (pinfunction "2_2") (pintype "passive"))
      (node (ref "R4_LF") (pin "1") (pinfunction "1_1") (pintype "passive"))
      (node (ref "U1") (pin "35") (pinfunction "VTUNE_35") (pintype "passive"))
    )
    (net (code "43") (name "Net-(Y1-CFO)") (class "Default")
      (node (ref "C14") (pin "1") (pinfunction "1_1") (pintype "passive"))
      (node (ref "R27") (pin "2") (pinfunction "2_2") (pintype "passive"))
      (node (ref "R32") (pin "2") (pinfunction "2_2") (pintype "passive"))
      (node (ref "Y1") (pin "5") (pinfunction "CFO_5") (pintype "output"))
    )
    (net (code "44") (name "Net-(Y1-FO)") (class "Default")
      (node (ref "C15") (pin "1") (pinfunction "1_1") (pintype "passive"))
      (node (ref "R28") (pin "2") (pinfunction "2_2") (pintype "passive"))
      (node (ref "R32") (pin "1") (pinfunction "1_1") (pintype "passive"))
      (node (ref "Y1") (pin "4") (pinfunction "FO_4") (pintype "output"))
    )
    (net (code "45") (name "Net-(Y1-VDD)") (class "Default")
      (node (ref "C13") (pin "1") (pinfunction "1_1") (pintype "passive"))
      (node (ref "R33") (pin "1") (pinfunction "1_1") (pintype "passive"))
      (node (ref "Y1") (pin "6") (pinfunction "VDD_6") (pintype "power_in"))
    )
    (net (code "46") (name "RampCLK") (class "Default")
      (node (ref "R7") (pin "2") (pinfunction "2_2") (pintype "passive"))
      (node (ref "R8") (pin "2") (pinfunction "2_2") (pintype "passive"))
      (node (ref "RampCLK_TP") (pin "1") (pintype "passive"))
      (node (ref "U1") (pin "30") (pinfunction "RAMPCLK/TRIG1_30") (pintype "input"))
    )
    (net (code "47") (name "RampDir") (class "Default")
      (node (ref "R5") (pin "1") (pinfunction "1_1") (pintype "passive"))
      (node (ref "R6") (pin "2") (pinfunction "2_2") (pintype "passive"))
      (node (ref "RampDIR_TP") (pin "1") (pintype "passive"))
      (node (ref "U1") (pin "32") (pinfunction "RAMPDIR/TRIG2_32") (pintype "input"))
    )
    (net (code "48") (name "SYNC") (class "Default")
      (node (ref "R22") (pin "2") (pinfunction "2_2") (pintype "passive"))
      (node (ref "R23") (pin "2") (pinfunction "2_2") (pintype "passive"))
      (node (ref "SYNC_TP") (pin "1") (pintype "passive"))
      (node (ref "U1") (pin "5") (pinfunction "SYNC_5") (pintype "input"))
    )
    (net (code "49") (name "SysRefReq") (class "Default")
      (node (ref "R10") (pin "2") (pinfunction "2_2") (pintype "passive"))
      (node (ref "R9") (pin "2") (pinfunction "2_2") (pintype "passive"))
      (node (ref "SysRefReq_TP") (pin "1") (pintype "passive"))
      (node (ref "U1") (pin "28") (pinfunction "SYSREFREQ_28") (pintype "input"))
    )
    (net (code "50") (name "Vcc") (class "Default")
      (node (ref "C16") (pin "2") (pinfunction "2_2") (pintype "passive"))
      (node (ref "C17") (pin "2") (pinfunction "2_2") (pintype "passive"))
      (node (ref "C3") (pin "2") (pinfunction "2_2") (pintype "passive"))
      (node (ref "C4") (pin "2") (pinfunction "2_2") (pintype "passive"))
      (node (ref "J3") (pin "2") (pinfunction "2_2") (pintype "passive"))
      (node (ref "L3") (pin "1") (pinfunction "1_1") (pintype "passive"))
      (node (ref "R2") (pin "1") (pinfunction "1_1") (pintype "passive"))
      (node (ref "R33") (pin "2") (pinfunction "2_2") (pintype "passive"))
      (node (ref "R36") (pin "2") (pinfunction "2_2") (pintype "passive"))
      (node (ref "R41") (pin "2") (pinfunction "2_2") (pintype "passive"))
      (node (ref "R42") (pin "1") (pinfunction "1_1") (pintype "passive"))
      (node (ref "R43") (pin "1") (pinfunction "1_1") (pintype "passive"))
      (node (ref "R44") (pin "1") (pinfunction "1_1") (pintype "passive"))
      (node (ref "Vcc_TP") (pin "1") (pintype "passive"))
    )
    (net (code "51") (name "VccRF") (class "Default")
      (node (ref "C1") (pin "2") (pinfunction "2_2") (pintype "passive"))
      (node (ref "C2") (pin "2") (pinfunction "2_2") (pintype "passive"))
      (node (ref "C8") (pin "2") (pinfunction "2_2") (pintype "passive"))
      (node (ref "C9") (pin "2") (pinfunction "2_2") (pintype "passive"))
      (node (ref "L1") (pin "1") (pinfunction "1_1") (pintype "passive"))
      (node (ref "L2") (pin "1") (pinfunction "1_1") (pintype "passive"))
      (node (ref "L3") (pin "2") (pinfunction "2_2") (pintype "passive"))
      (node (ref "R45") (pin "1") (pinfunction "1_1") (pintype "passive"))
      (node (ref "VccRF_TP") (pin "1") (pintype "passive"))
    )
    (net (code "52") (name "unconnected-(J1-Pad5)") (class "Default")
      (node (ref "J1") (pin "5") (pinfunction "5_5") (pintype "passive+no_connect"))
    )
    (net (code "53") (name "unconnected-(Y1-NC-Pad1)") (class "Default")
      (node (ref "Y1") (pin "1") (pinfunction "NC_1") (pintype "passive+no_connect"))
    )
    (net (code "54") (name "unconnected-(Y1-NC-Pad2)") (class "Default")
      (node (ref "Y1") (pin "2") (pinfunction "NC_2") (pintype "passive+no_connect"))
    )
  )
)
